# CAN.net
KiCad netlist of a schematic drawn in Altium Designer
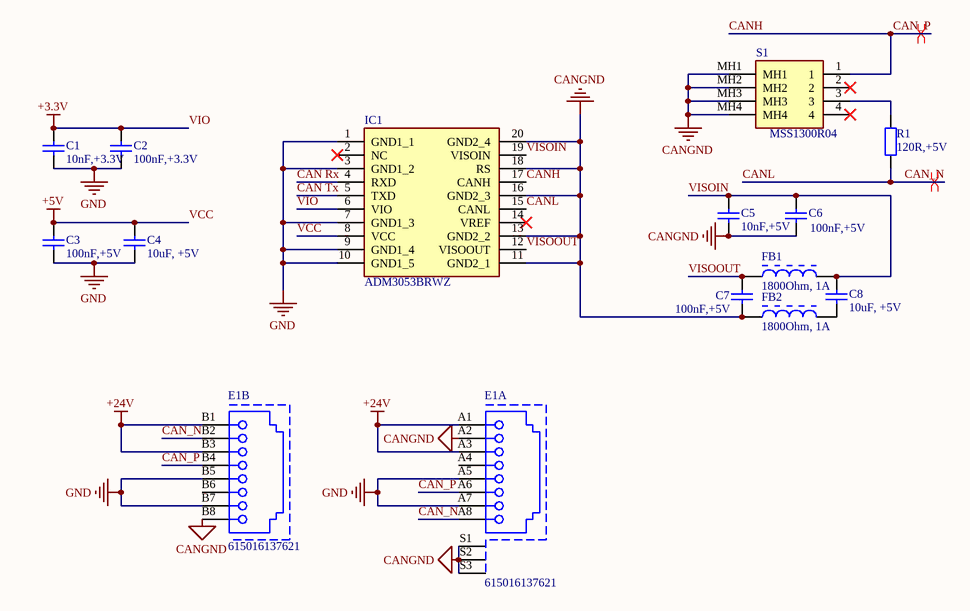
[diagram p0: CAN.SchDoc]

(export (version "E")
  (design (tool "Eeschema 10.0.6"))
  (components
    (comp (ref "C1")
      (value "10nF,+3.3V")
      (footprint "C 0805")
      (description "WCAP-CSGP Multilayer Ceramic Chip Capacitor, General Purpose, size 0805, X7R, 47nF, 100V")
      (fields
        (field (name "MANUFACTURER PART NUMBER") "885012207126")
        (field (name "MANUFACTURER") "Wurth Elektronik")
      )
      (libsource (lib "TelemetriaV2") (part "885012207126_6"))
    )
    (comp (ref "C2")
      (value "100nF,+3.3V")
      (footprint "C 1206")
      (description "WCAP-CSGP General Purpose Ceramic Capacitors, size 1206, 2.2uF, +/-10%, 10VDC")
      (fields (field (name "PART NUMBER") "885012208015") (field (name "PUBLISHER") "Wurth Elektronik"))
      (libsource (lib "TelemetriaV2") (part "885012208015_1"))
    )
    (comp (ref "C3")
      (value "100nF,+5V")
      (footprint "C 1206")
      (description "WCAP-CSGP General Purpose Ceramic Capacitors, size 1206, 1uF, +/-10%, 10VDC")
      (fields (field (name "PART NUMBER") "885012208013") (field (name "PUBLISHER") "Wurth Elektronik"))
      (libsource (lib "TelemetriaV2") (part "885012208013_4"))
    )
    (comp (ref "C4")
      (value "10uF, +5V")
      (footprint "C 1206")
      (description "WCAP-CSGP General Purpose Ceramic Capacitors, size 1206, 1uF, +/-10%, 10VDC")
      (fields (field (name "PART NUMBER") "885012208013") (field (name "PUBLISHER") "Wurth Elektronik"))
      (libsource (lib "TelemetriaV2") (part "885012208013_5"))
    )
    (comp (ref "C5")
      (value "10nF,+5V")
      (footprint "C 0805")
      (description "WCAP-CSGP Multilayer Ceramic Chip Capacitor, General Purpose, size 0805, X7R, 47nF, 100V")
      (fields
        (field (name "MANUFACTURER PART NUMBER") "885012207126")
        (field (name "MANUFACTURER") "Wurth Elektronik")
      )
      (libsource (lib "TelemetriaV2") (part "885012207126_6"))
    )
    (comp (ref "C6")
      (value "100nF,+5V")
      (footprint "C 1206")
      (description "WCAP-CSGP General Purpose Ceramic Capacitors, size 1206, 1uF, +/-10%, 10VDC")
      (fields (field (name "PART NUMBER") "885012208013") (field (name "PUBLISHER") "Wurth Elektronik"))
      (libsource (lib "TelemetriaV2") (part "885012208013_4"))
    )
    (comp (ref "C7")
      (value "100nF,+5V")
      (footprint "C 1206")
      (description "WCAP-CSGP General Purpose Ceramic Capacitors, size 1206, 1uF, +/-10%, 10VDC")
      (fields (field (name "PART NUMBER") "885012208013") (field (name "PUBLISHER") "Wurth Elektronik"))
      (libsource (lib "TelemetriaV2") (part "885012208013_4"))
    )
    (comp (ref "C8")
      (value "10uF, +5V")
      (footprint "C 1206")
      (description "WCAP-CSGP General Purpose Ceramic Capacitors, size 1206, 1uF, +/-10%, 10VDC")
      (fields (field (name "PART NUMBER") "885012208013") (field (name "PUBLISHER") "Wurth Elektronik"))
      (libsource (lib "TelemetriaV2") (part "885012208013_5"))
    )
    (comp (ref "E1")
      (value "615016137621")
      (footprint "Ethernet2")
      (description "WR-MJ Modular Jack THT Horizontal Shielded Dual Port 8P8C Tab Down")
      (fields (field (name "PUBLISHER") "Wurth Elektronik"))
      (libsource (lib "TelemetriaV2") (part "615016137621"))
    )
    (comp (ref "FB1")
      (value "1800Ohm, 1A")
      (footprint "F 0805")
      (description "WE-CBF SMT EMI Suppression Ferrite Bead, size 0805, 1800Ohm, 1A")
      (fields
        (field (name "MANUFACTURER PART NUMBER") "742792090")
        (field (name "MANUFACTURER") "Wurth Elektronik")
      )
      (libsource (lib "TelemetriaV2") (part "742792090"))
    )
    (comp (ref "FB2")
      (value "1800Ohm, 1A")
      (footprint "F 0805")
      (description "WE-CBF SMT EMI Suppression Ferrite Bead, size 0805, 1800Ohm, 1A")
      (fields
        (field (name "MANUFACTURER PART NUMBER") "742792090")
        (field (name "MANUFACTURER") "Wurth Elektronik")
      )
      (libsource (lib "TelemetriaV2") (part "742792090"))
    )
    (comp (ref "IC1")
      (value "ADM3053BRWZ")
      (footprint "SamacSys:SOIC127P1032X265-20N")
      (description "Integrated Circuit")
      (fields (field (name "MOUSER PART NUMBER") "584-ADM3053BRWZ"))
      (libsource (lib "*") (part "ADM3053BRWZ"))
    )
    (comp (ref "R1")
      (value "120R,+5V")
      (footprint "R 0805")
      (description "WRIS-KSKE SMT Thick Film Resistor, size 0805, 1Ohm, 0.33W")
      (fields
        (field (name "MANUFACTURER") "Wurth Elektronik")
        (field (name "MANUFACTURER PART NUMBER") "560050320011")
      )
      (libsource (lib "TelemetriaV2") (part "560050320011_9"))
    )
    (comp (ref "S1")
      (value "MSS1300R04")
      (footprint "SamacSys:MSS1300R04")
      (description "Switch")
      (fields (field (name "MOUSER PART NUMBER") "506-MSS1300R04"))
      (libsource (lib "*") (part "MSS1300R04"))
    )
  )
  (nets
    (net (code "1") (name "+3.3V") (class "Default")
      (node (ref "C1") (pin "2") (pinfunction "2_2") (pintype "passive"))
      (node (ref "C2") (pin "2") (pinfunction "2_2") (pintype "passive"))
      (node (ref "IC1") (pin "6") (pinfunction "VIO_6") (pintype "passive"))
    )
    (net (code "2") (name "+5V") (class "Default")
      (node (ref "C3") (pin "2") (pinfunction "2_2") (pintype "passive"))
      (node (ref "C4") (pin "2") (pinfunction "2_2") (pintype "passive"))
      (node (ref "IC1") (pin "8") (pinfunction "VCC_8") (pintype "passive"))
    )
    (net (code "3") (name "+24V") (class "Default")
      (node (ref "E1") (pin "A1") (pinfunction "A1_A1") (pintype "passive"))
      (node (ref "E1") (pin "A3") (pinfunction "A3_A3") (pintype "passive"))
      (node (ref "E1") (pin "B1") (pinfunction "B1_B1") (pintype "passive"))
      (node (ref "E1") (pin "B3") (pinfunction "B3_B3") (pintype "passive"))
    )
    (net (code "4") (name "/CAN Rx") (class "Default")
      (node (ref "IC1") (pin "4") (pinfunction "RXD_4") (pintype "passive"))
    )
    (net (code "5") (name "/CAN Tx") (class "Default")
      (node (ref "IC1") (pin "5") (pinfunction "TXD_5") (pintype "passive"))
    )
    (net (code "6") (name "/CANH") (class "Default")
      (node (ref "E1") (pin "A6") (pinfunction "A6_A6") (pintype "passive"))
      (node (ref "E1") (pin "B4") (pinfunction "B4_B4") (pintype "passive"))
      (node (ref "IC1") (pin "17") (pinfunction "CANH_17") (pintype "passive"))
      (node (ref "S1") (pin "1") (pinfunction "1_1") (pintype "passive"))
    )
    (net (code "7") (name "/CANL") (class "Default")
      (node (ref "E1") (pin "A8") (pinfunction "A8_A8") (pintype "passive"))
      (node (ref "E1") (pin "B2") (pinfunction "B2_B2") (pintype "passive"))
      (node (ref "IC1") (pin "15") (pinfunction "CANL_15") (pintype "passive"))
      (node (ref "R1") (pin "1") (pinfunction "1_1") (pintype "passive"))
    )
    (net (code "8") (name "/VISOIN") (class "Default")
      (node (ref "C5") (pin "2") (pinfunction "2_2") (pintype "passive"))
      (node (ref "C6") (pin "2") (pinfunction "2_2") (pintype "passive"))
      (node (ref "C8") (pin "2") (pinfunction "2_2") (pintype "passive"))
      (node (ref "FB1") (pin "2") (pinfunction "2_2") (pintype "passive"))
      (node (ref "IC1") (pin "19") (pinfunction "VISOIN_19") (pintype "passive"))
    )
    (net (code "9") (name "/VISOOUT") (class "Default")
      (node (ref "C7") (pin "2") (pinfunction "2_2") (pintype "passive"))
      (node (ref "FB1") (pin "1") (pinfunction "1_1") (pintype "passive"))
      (node (ref "IC1") (pin "12") (pinfunction "VISOOUT_12") (pintype "passive"))
    )
    (net (code "10") (name "CANGND") (class "Default")
      (node (ref "C5") (pin "1") (pinfunction "1_1") (pintype "passive"))
      (node (ref "C6") (pin "1") (pinfunction "1_1") (pintype "passive"))
      (node (ref "C7") (pin "1") (pinfunction "1_1") (pintype "passive"))
      (node (ref "E1") (pin "A2") (pinfunction "A2_A2") (pintype "passive"))
      (node (ref "E1") (pin "B8") (pinfunction "B8_B8") (pintype "passive"))
      (node (ref "E1") (pin "S1") (pinfunction "S1_S1") (pintype "passive"))
      (node (ref "E1") (pin "S2") (pinfunction "S2_S2") (pintype "passive"))
      (node (ref "E1") (pin "S3") (pinfunction "S3_S3") (pintype "passive"))
      (node (ref "FB2") (pin "1") (pinfunction "1_1") (pintype "passive"))
      (node (ref "IC1") (pin "11") (pinfunction "GND2_1_11") (pintype "passive"))
      (node (ref "IC1") (pin "13") (pinfunction "GND2_2_13") (pintype "passive"))
      (node (ref "IC1") (pin "16") (pinfunction "GND2_3_16") (pintype "passive"))
      (node (ref "IC1") (pin "18") (pinfunction "RS_18") (pintype "passive"))
      (node (ref "IC1") (pin "20") (pinfunction "GND2_4_20") (pintype "passive"))
      (node (ref "S1") (pin "MH1") (pinfunction "MH1_MH1") (pintype "passive"))
      (node (ref "S1") (pin "MH2") (pinfunction "MH2_MH2") (pintype "passive"))
      (node (ref "S1") (pin "MH3") (pinfunction "MH3_MH3") (pintype "passive"))
      (node (ref "S1") (pin "MH4") (pinfunction "MH4_MH4") (pintype "passive"))
    )
    (net (code "11") (name "GND") (class "Default")
      (node (ref "C1") (pin "1") (pinfunction "1_1") (pintype "passive"))
      (node (ref "C2") (pin "1") (pinfunction "1_1") (pintype "passive"))
      (node (ref "C3") (pin "1") (pinfunction "1_1") (pintype "passive"))
      (node (ref "C4") (pin "1") (pinfunction "1_1") (pintype "passive"))
      (node (ref "E1") (pin "A5") (pinfunction "A5_A5") (pintype "passive"))
      (node (ref "E1") (pin "A7") (pinfunction "A7_A7") (pintype "passive"))
      (node (ref "E1") (pin "B5") (pinfunction "B5_B5") (pintype "passive"))
      (node (ref "E1") (pin "B7") (pinfunction "B7_B7") (pintype "passive"))
      (node (ref "IC1") (pin "1") (pinfunction "GND1_1_1") (pintype "passive"))
      (node (ref "IC1") (pin "10") (pinfunction "GND1_5_10") (pintype "passive"))
      (node (ref "IC1") (pin "3") (pinfunction "GND1_2_3") (pintype "passive"))
      (node (ref "IC1") (pin "7") (pinfunction "GND1_3_7") (pintype "passive"))
      (node (ref "IC1") (pin "9") (pinfunction "GND1_4_9") (pintype "passive"))
    )
    (net (code "12") (name "Net-(C8-Pad1)") (class "Default")
      (node (ref "C8") (pin "1") (pinfunction "1_1") (pintype "passive"))
      (node (ref "FB2") (pin "2") (pinfunction "2_2") (pintype "passive"))
    )
    (net (code "13") (name "Net-(R1-Pad2)") (class "Default")
      (node (ref "R1") (pin "2") (pinfunction "2_2") (pintype "passive"))
      (node (ref "S1") (pin "3") (pinfunction "3_3") (pintype "passive"))
    )
    (net (code "14") (name "unconnected-(E1-PadA4)") (class "Default")
      (node (ref "E1") (pin "A4") (pinfunction "A4_A4") (pintype "passive"))
    )
    (net (code "15") (name "unconnected-(E1-PadB6)") (class "Default")
      (node (ref "E1") (pin "B6") (pinfunction "B6_B6") (pintype "passive"))
    )
    (net (code "16") (name "unconnected-(IC1-NC-Pad2)") (class "Default")
      (node (ref "IC1") (pin "2") (pinfunction "NC_2") (pintype "passive+no_connect"))
    )
    (net (code "17") (name "unconnected-(IC1-VREF-Pad14)") (class "Default")
      (node (ref "IC1") (pin "14") (pinfunction "VREF_14") (pintype "passive+no_connect"))
    )
    (net (code "18") (name "unconnected-(S1-Pad2)") (class "Default")
      (node (ref "S1") (pin "2") (pinfunction "2_2") (pintype "passive+no_connect"))
    )
    (net (code "19") (name "unconnected-(S1-Pad4)") (class "Default")
      (node (ref "S1") (pin "4") (pinfunction "4_4") (pintype "passive+no_connect"))
    )
  )
)
